# Power.net
KiCad netlist of a schematic drawn in Altium Designer
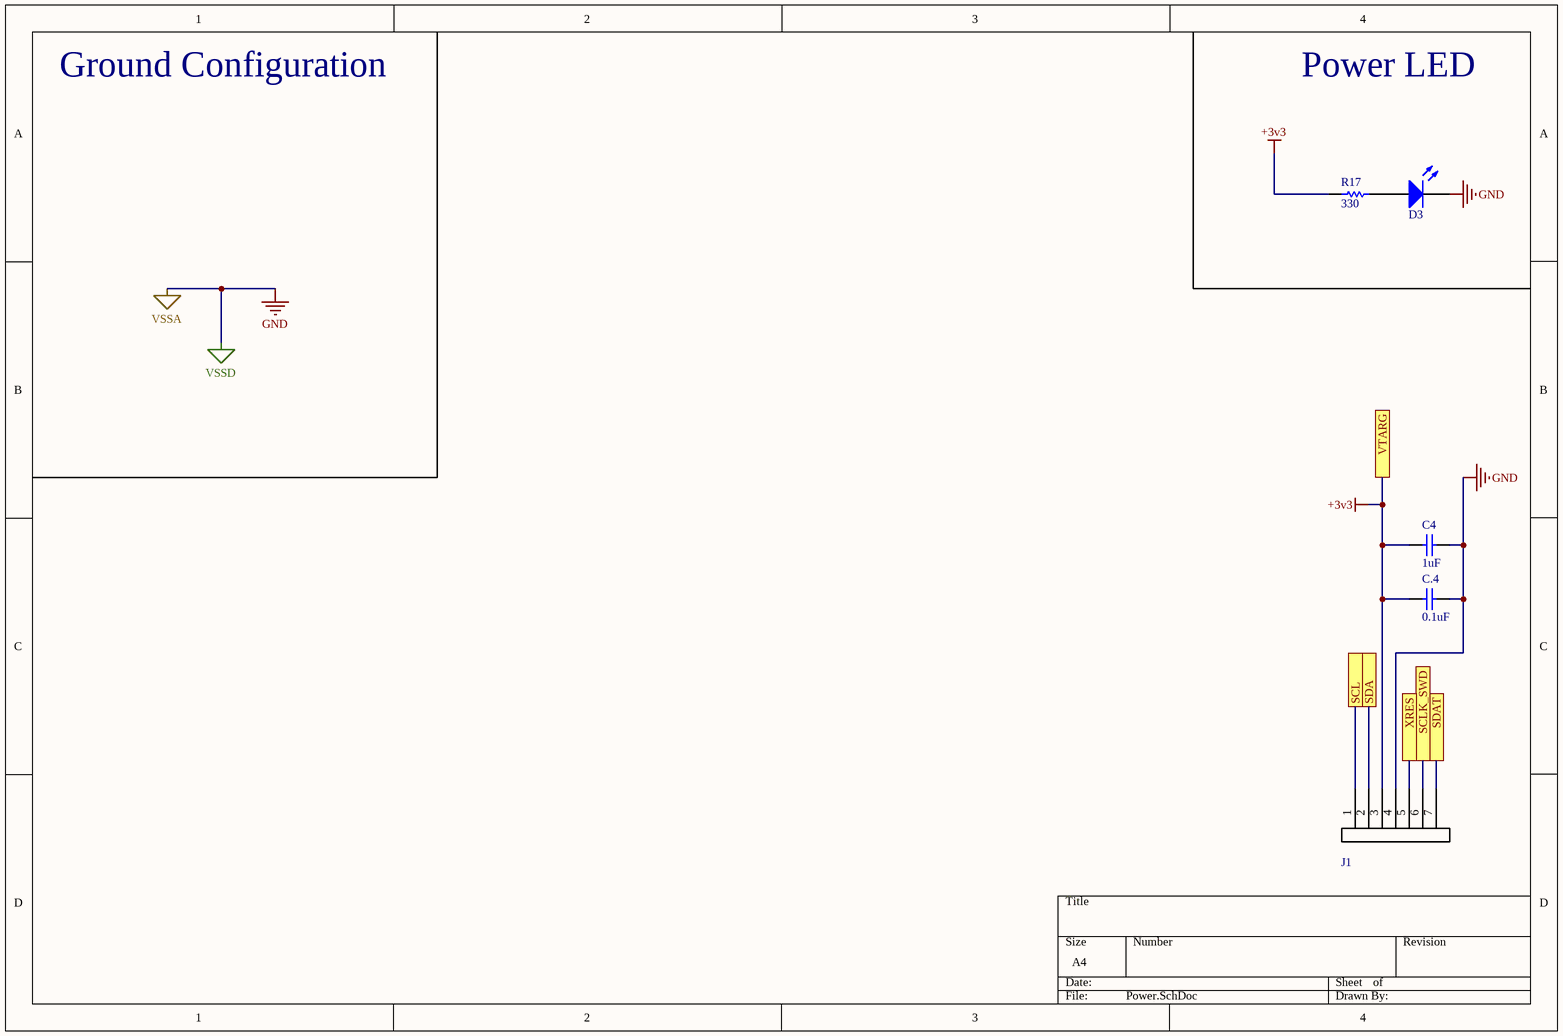
[diagram p0: Power.SchDoc]

(export (version "E")
  (design (tool "Eeschema 10.0.6"))
  (components
    (comp (ref "C.4")
      (value "0.1uF")
      (footprint "CAPC1005X56X25ML10T15")
      (fields
        (field (name "MANUFACTURER") "AVX Interconnect / Elco")
        (field (name "PART NUMBER") "04026D105KAT2A")
      )
      (libsource (lib "Altium Content Vault") (part "CAP"))
    )
    (comp (ref "C4")
      (value "1uF")
      (footprint "CAPC1005X56X25ML10T15")
      (fields
        (field (name "MANUFACTURER") "AVX Interconnect / Elco")
        (field (name "PART NUMBER") "04026D105KAT2A")
      )
      (libsource (lib "Altium Content Vault") (part "CAP"))
    )
    (comp (ref "D3")
      (value "150060BS75000")
      (footprint "0603_A")
      (description "SMD mono-color Chip LED, WL-SMCW, Blue")
      (fields (field (name "MANUFACTURER") "Wuerth Elektronik"))
      (libsource (lib "Altium Content Vault") (part "WE-LED_K1A2-2"))
    )
    (comp (ref "J1")
      (value "BM07B-NSHSS-TBT (LF)(SN)")
      (footprint "BM07B-NSHSS-TBT (LF)(SN)")
      (libsource (lib "Pads") (part "BM07B-NSHSS-TBT (LF)(SN)"))
    )
    (comp (ref "R17")
      (value "330")
      (footprint "RESC1005X40X25ML05T10")
      (fields (field (name "PART NUMBER") "RC0402JR-072KL") (field (name "MANUFACTURER") "Yageo / Phycomp"))
      (libsource (lib "Altium Content Vault") (part "RES"))
    )
  )
  (nets
    (net (code "1") (name "+3v3") (class "Default")
      (node (ref "C.4") (pin "1") (pinfunction "1_1") (pintype "passive"))
      (node (ref "C4") (pin "1") (pinfunction "1_1") (pintype "passive"))
      (node (ref "J1") (pin "3") (pinfunction "0_3") (pintype "passive"))
      (node (ref "R17") (pin "1") (pinfunction "1_1") (pintype "passive"))
    )
    (net (code "2") (name "/SCL") (class "Default")
      (node (ref "J1") (pin "1") (pinfunction "0_1") (pintype "passive"))
    )
    (net (code "3") (name "/SCLK_SWD") (class "Default")
      (node (ref "J1") (pin "6") (pinfunction "0_6") (pintype "passive"))
    )
    (net (code "4") (name "/SDA") (class "Default")
      (node (ref "J1") (pin "2") (pinfunction "0_2") (pintype "passive"))
    )
    (net (code "5") (name "/SDAT") (class "Default")
      (node (ref "J1") (pin "7") (pinfunction "0_7") (pintype "passive"))
    )
    (net (code "6") (name "/XRES") (class "Default")
      (node (ref "J1") (pin "5") (pinfunction "0_5") (pintype "passive"))
    )
    (net (code "7") (name "GND") (class "Default")
      (node (ref "C.4") (pin "2") (pinfunction "2_2") (pintype "passive"))
      (node (ref "C4") (pin "2") (pinfunction "2_2") (pintype "passive"))
      (node (ref "D3") (pin "1") (pinfunction "K_1") (pintype "passive"))
      (node (ref "J1") (pin "4") (pinfunction "0_4") (pintype "passive"))
    )
    (net (code "8") (name "Net-(D3-A)") (class "Default")
      (node (ref "D3") (pin "2") (pinfunction "A_2") (pintype "passive"))
      (node (ref "R17") (pin "2") (pinfunction "2_2") (pintype "passive"))
    )
  )
)
